# Motion_Sensor_Schematic.net
KiCad netlist of a schematic drawn in Altium Designer
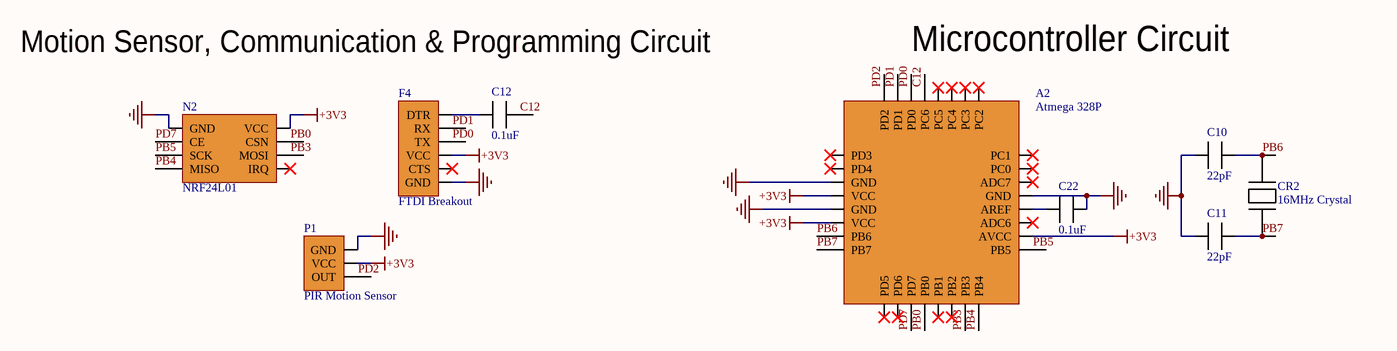
[diagram p0: Motion Sensor Schematic.SchDoc]

(export (version "E")
  (design (tool "Eeschema 10.0.6"))
  (components
    (comp (ref "A2")
      (value "Atmega 328P")
      (footprint "ATMega328P")
      (description "IC MCU 8BIT 32KB FLASH 32TQFP")
      (fields
        (field (name "MANUFACTURER") "Microchip")
        (field (name "MANUFACTURER PART NUMBER") "ATMEGA328PB-AUR")
      )
      (libsource (lib "Schematic Library") (part "ATMEGA328PB-AUR"))
    )
    (comp (ref "C10")
      (value "22pF")
      (footprint "22pF Capacitor")
      (description "Cap Ceramic 22pF 50V C0G 5% SMD 0603 125C Paper T/R")
      (fields
        (field (name "MANUFACTURER") "Kyocera AVX")
        (field (name "MANUFACTURER PART NUMBER") "06035A220JAT2A")
      )
      (libsource (lib "Schematic Library") (part "06035A220JAT2A"))
    )
    (comp (ref "C11")
      (value "22pF")
      (footprint "22pF Capacitor")
      (description "Cap Ceramic 22pF 50V C0G 5% SMD 0603 125C Paper T/R")
      (fields
        (field (name "MANUFACTURER") "Kyocera AVX")
        (field (name "MANUFACTURER PART NUMBER") "06035A220JAT2A")
      )
      (libsource (lib "Schematic Library") (part "06035A220JAT2A"))
    )
    (comp (ref "C12")
      (value "0.1uF")
      (footprint "0.1uF Capacitor")
      (description "CAP CER 0.1UF 25V X7R 0603")
      (fields
        (field (name "MANUFACTURER") "Kyocera AVX")
        (field (name "MANUFACTURER PART NUMBER") "06033C104KAT4A")
      )
      (libsource (lib "Schematic Library") (part "06033C104KAT4A"))
    )
    (comp (ref "C22")
      (value "0.1uF")
      (footprint "0.1uF Capacitor")
      (description "CAP CER 0.1UF 25V X7R 0603")
      (fields
        (field (name "MANUFACTURER") "Kyocera AVX")
        (field (name "MANUFACTURER PART NUMBER") "06033C104KAT4A")
      )
      (libsource (lib "Schematic Library") (part "06033C104KAT4A"))
    )
    (comp (ref "CR2")
      (value "16MHz Crystal")
      (footprint "16MHz Crystal")
      (description "CRYSTAL 16.0000MHZ 20PF SMD")
      (fields
        (field (name "MANUFACTURER") "ECS International")
        (field (name "MANUFACTURER PART NUMBER") "ECS-160-20-3X-TR")
      )
      (libsource (lib "Schematic Library") (part "ECS-160-20-3X-TR"))
    )
    (comp (ref "F4")
      (value "FTDI Breakout")
      (footprint "FTDI")
      (description "FTDI USB to TTL serial converter module")
      (libsource (lib "Schematic Library") (part "FTDI"))
    )
    (comp (ref "N2")
      (value "NRF24L01")
      (footprint "NRF24L01")
      (description "3.3V NRF24L01 WIRELESS RF MODULE")
      (libsource (lib "Schematic Library") (part "NRF24L01"))
    )
    (comp (ref "P1")
      (value "PIR Motion Sensor")
      (footprint "PIR Motion Sensor")
      (description "Pyroelectric IR sensor, 555-28027, Parallax")
      (fields (field (name "MANUFACTURER") "Parallax") (field (name "MANUFACTURER PART NUMBER") "555-28027"))
      (libsource (lib "Schematic Library") (part "555-28027"))
    )
  )
  (nets
    (net (code "1") (name "+3V3") (class "Default")
      (node (ref "A2") (pin "18") (pinfunction "AVCC_18") (pintype "passive"))
      (node (ref "A2") (pin "4") (pinfunction "VCC_4") (pintype "passive"))
      (node (ref "A2") (pin "6") (pinfunction "VCC_6") (pintype "passive"))
      (node (ref "F4") (pin "4") (pinfunction "VCC_4") (pintype "passive"))
      (node (ref "N2") (pin "5") (pinfunction "VCC_5") (pintype "passive"))
      (node (ref "P1") (pin "2") (pinfunction "VCC_2") (pintype "passive"))
    )
    (net (code "2") (name "/C12") (class "Default")
      (node (ref "A2") (pin "29") (pinfunction "PC6_29") (pintype "passive"))
      (node (ref "C12") (pin "2") (pinfunction "2_2") (pintype "passive"))
    )
    (net (code "3") (name "/PB0") (class "Default")
      (node (ref "A2") (pin "12") (pinfunction "PB0_12") (pintype "passive"))
      (node (ref "N2") (pin "6") (pinfunction "CSN_6") (pintype "passive"))
    )
    (net (code "4") (name "/PB3") (class "Default")
      (node (ref "A2") (pin "15") (pinfunction "PB3_15") (pintype "passive"))
      (node (ref "N2") (pin "7") (pinfunction "MOSI_7") (pintype "passive"))
    )
    (net (code "5") (name "/PB4") (class "Default")
      (node (ref "A2") (pin "16") (pinfunction "PB4_16") (pintype "passive"))
      (node (ref "N2") (pin "4") (pinfunction "MISO_4") (pintype "passive"))
    )
    (net (code "6") (name "/PB5") (class "Default")
      (node (ref "A2") (pin "17") (pinfunction "PB5_17") (pintype "passive"))
      (node (ref "N2") (pin "3") (pinfunction "SCK_3") (pintype "passive"))
    )
    (net (code "7") (name "/PB6") (class "Default")
      (node (ref "A2") (pin "7") (pinfunction "PB6_7") (pintype "passive"))
      (node (ref "C10") (pin "2") (pinfunction "2_2") (pintype "passive"))
      (node (ref "CR2") (pin "2") (pinfunction "2_2") (pintype "passive"))
    )
    (net (code "8") (name "/PB7") (class "Default")
      (node (ref "A2") (pin "8") (pinfunction "PB7_8") (pintype "passive"))
      (node (ref "C11") (pin "2") (pinfunction "2_2") (pintype "passive"))
      (node (ref "CR2") (pin "1") (pinfunction "1_1") (pintype "passive"))
    )
    (net (code "9") (name "/PD0") (class "Default")
      (node (ref "A2") (pin "30") (pinfunction "PD0_30") (pintype "passive"))
      (node (ref "F4") (pin "3") (pinfunction "TX_3") (pintype "passive"))
    )
    (net (code "10") (name "/PD1") (class "Default")
      (node (ref "A2") (pin "31") (pinfunction "PD1_31") (pintype "passive"))
      (node (ref "F4") (pin "2") (pinfunction "RX_2") (pintype "passive"))
    )
    (net (code "11") (name "/PD2") (class "Default")
      (node (ref "A2") (pin "32") (pinfunction "PD2_32") (pintype "passive"))
      (node (ref "P1") (pin "3") (pinfunction "OUT_3") (pintype "passive"))
    )
    (net (code "12") (name "/PD7") (class "Default")
      (node (ref "A2") (pin "11") (pinfunction "PD7_11") (pintype "passive"))
      (node (ref "N2") (pin "2") (pinfunction "CE_2") (pintype "passive"))
    )
    (net (code "13") (name "GND") (class "Default")
      (node (ref "A2") (pin "21") (pinfunction "GND_21") (pintype "passive"))
      (node (ref "A2") (pin "3") (pinfunction "GND_3") (pintype "passive"))
      (node (ref "A2") (pin "5") (pinfunction "GND_5") (pintype "passive"))
      (node (ref "C10") (pin "1") (pinfunction "1_1") (pintype "passive"))
      (node (ref "C11") (pin "1") (pinfunction "1_1") (pintype "passive"))
      (node (ref "C22") (pin "2") (pinfunction "2_2") (pintype "passive"))
      (node (ref "F4") (pin "6") (pinfunction "GND_6") (pintype "passive"))
      (node (ref "N2") (pin "1") (pinfunction "GND_1") (pintype "passive"))
      (node (ref "P1") (pin "1") (pinfunction "GND_1") (pintype "passive"))
    )
    (net (code "14") (name "Net-(A2-AREF)") (class "Default")
      (node (ref "A2") (pin "20") (pinfunction "AREF_20") (pintype "passive"))
      (node (ref "C22") (pin "1") (pinfunction "1_1") (pintype "passive"))
    )
    (net (code "15") (name "Net-(F4-DTR)") (class "Default")
      (node (ref "C12") (pin "1") (pinfunction "1_1") (pintype "passive"))
      (node (ref "F4") (pin "1") (pinfunction "DTR_1") (pintype "passive"))
    )
    (net (code "16") (name "unconnected-(A2-ADC6-Pad19)") (class "Default")
      (node (ref "A2") (pin "19") (pinfunction "ADC6_19") (pintype "passive+no_connect"))
    )
    (net (code "17") (name "unconnected-(A2-ADC7-Pad22)") (class "Default")
      (node (ref "A2") (pin "22") (pinfunction "ADC7_22") (pintype "passive+no_connect"))
    )
    (net (code "18") (name "unconnected-(A2-PB1-Pad13)") (class "Default")
      (node (ref "A2") (pin "13") (pinfunction "PB1_13") (pintype "passive+no_connect"))
    )
    (net (code "19") (name "unconnected-(A2-PB2-Pad14)") (class "Default")
      (node (ref "A2") (pin "14") (pinfunction "PB2_14") (pintype "passive+no_connect"))
    )
    (net (code "20") (name "unconnected-(A2-PC0-Pad23)") (class "Default")
      (node (ref "A2") (pin "23") (pinfunction "PC0_23") (pintype "passive+no_connect"))
    )
    (net (code "21") (name "unconnected-(A2-PC1-Pad24)") (class "Default")
      (node (ref "A2") (pin "24") (pinfunction "PC1_24") (pintype "passive+no_connect"))
    )
    (net (code "22") (name "unconnected-(A2-PC2-Pad25)") (class "Default")
      (node (ref "A2") (pin "25") (pinfunction "PC2_25") (pintype "passive+no_connect"))
    )
    (net (code "23") (name "unconnected-(A2-PC3-Pad26)") (class "Default")
      (node (ref "A2") (pin "26") (pinfunction "PC3_26") (pintype "passive+no_connect"))
    )
    (net (code "24") (name "unconnected-(A2-PC4-Pad27)") (class "Default")
      (node (ref "A2") (pin "27") (pinfunction "PC4_27") (pintype "passive+no_connect"))
    )
    (net (code "25") (name "unconnected-(A2-PC5-Pad28)") (class "Default")
      (node (ref "A2") (pin "28") (pinfunction "PC5_28") (pintype "passive+no_connect"))
    )
    (net (code "26") (name "unconnected-(A2-PD3-Pad1)") (class "Default")
      (node (ref "A2") (pin "1") (pinfunction "PD3_1") (pintype "passive+no_connect"))
    )
    (net (code "27") (name "unconnected-(A2-PD4-Pad2)") (class "Default")
      (node (ref "A2") (pin "2") (pinfunction "PD4_2") (pintype "passive+no_connect"))
    )
    (net (code "28") (name "unconnected-(A2-PD5-Pad9)") (class "Default")
      (node (ref "A2") (pin "9") (pinfunction "PD5_9") (pintype "passive+no_connect"))
    )
    (net (code "29") (name "unconnected-(A2-PD6-Pad10)") (class "Default")
      (node (ref "A2") (pin "10") (pinfunction "PD6_10") (pintype "passive+no_connect"))
    )
    (net (code "30") (name "unconnected-(F4-CTS-Pad5)") (class "Default")
      (node (ref "F4") (pin "5") (pinfunction "CTS_5") (pintype "passive+no_connect"))
    )
    (net (code "31") (name "unconnected-(N2-IRQ-Pad8)") (class "Default")
      (node (ref "N2") (pin "8") (pinfunction "IRQ_8") (pintype "passive+no_connect"))
    )
  )
)
